# 06_SBCStage_v1.net
KiCad netlist of a schematic drawn in EAGLE
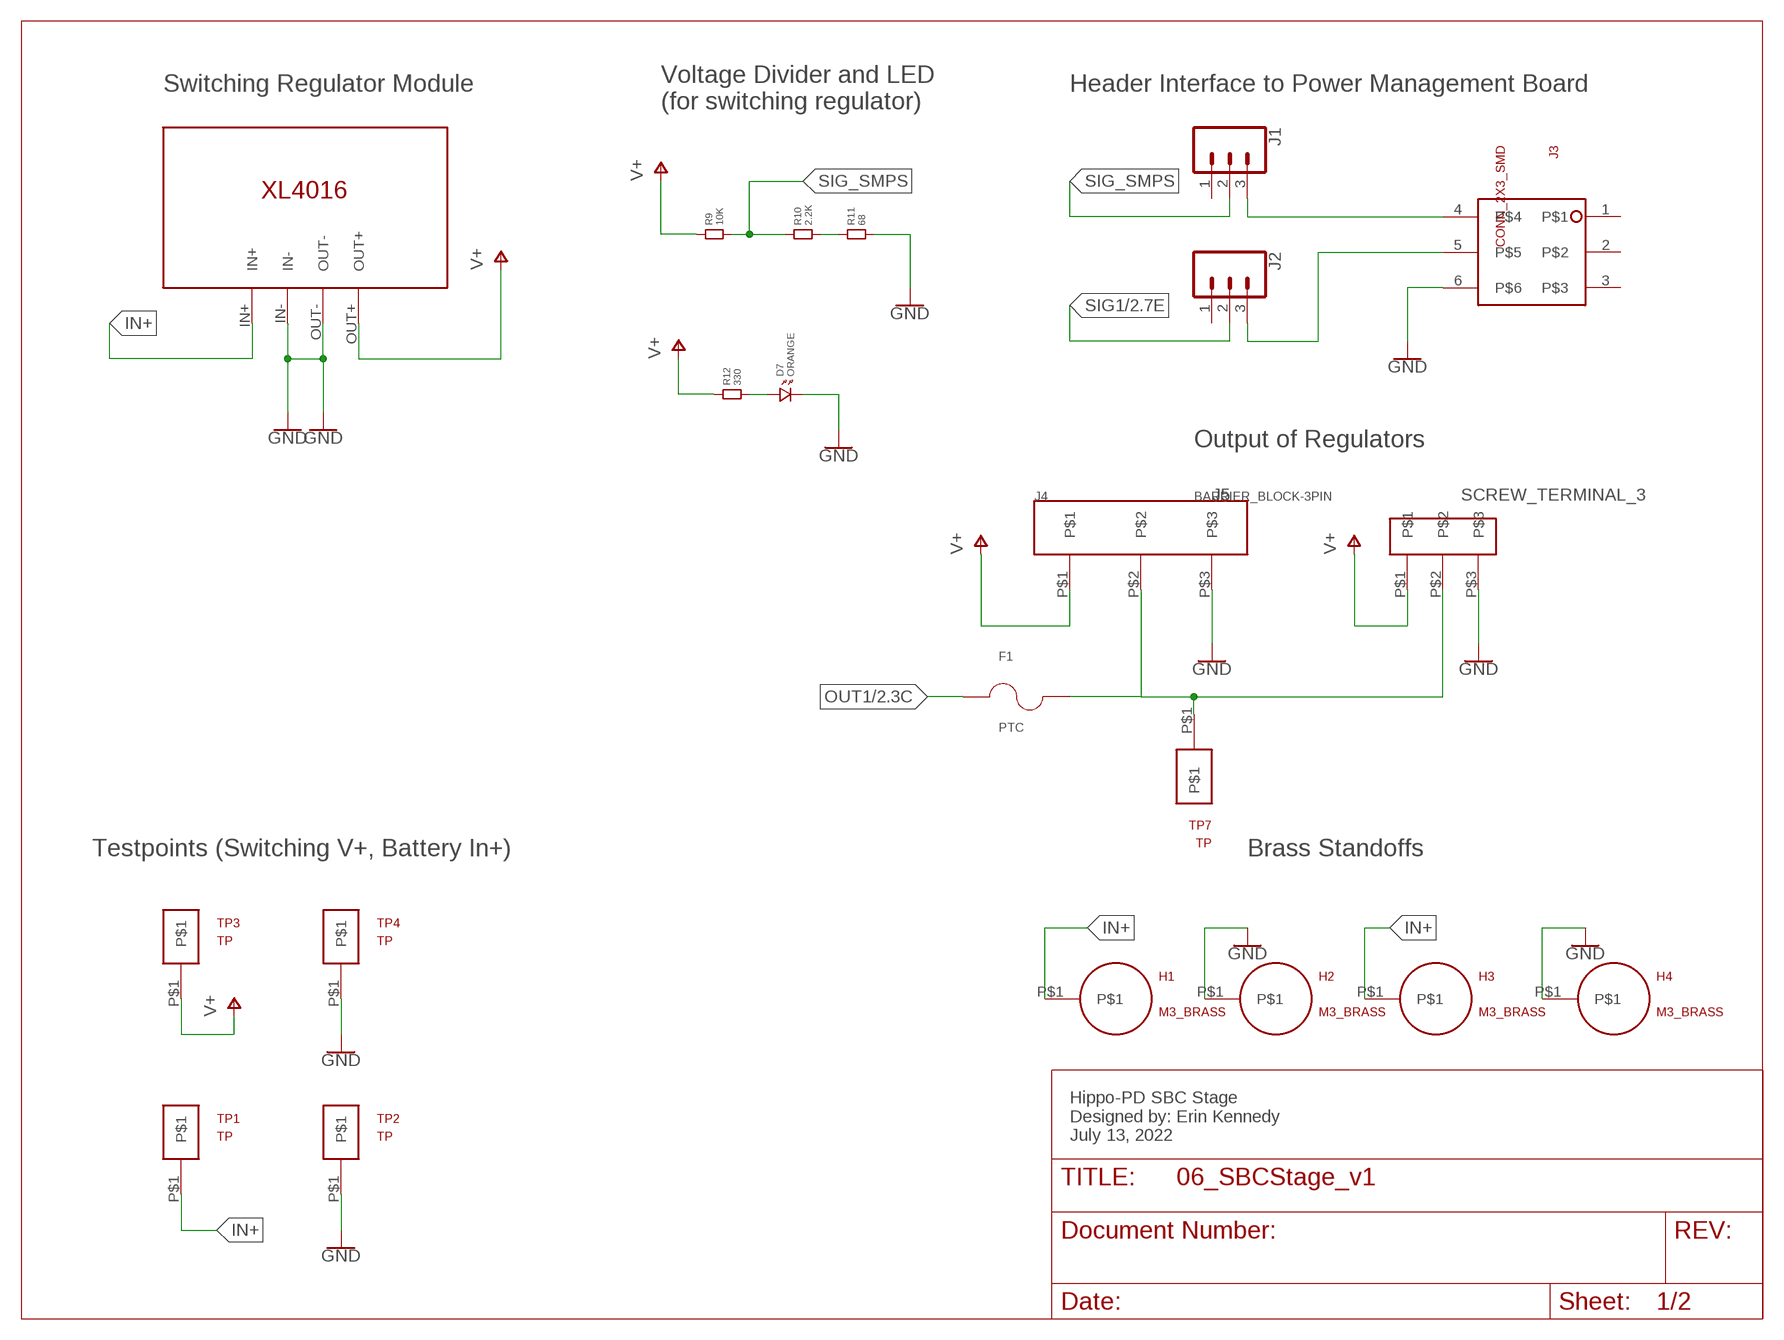
[diagram p0: schematic, sheet 1]
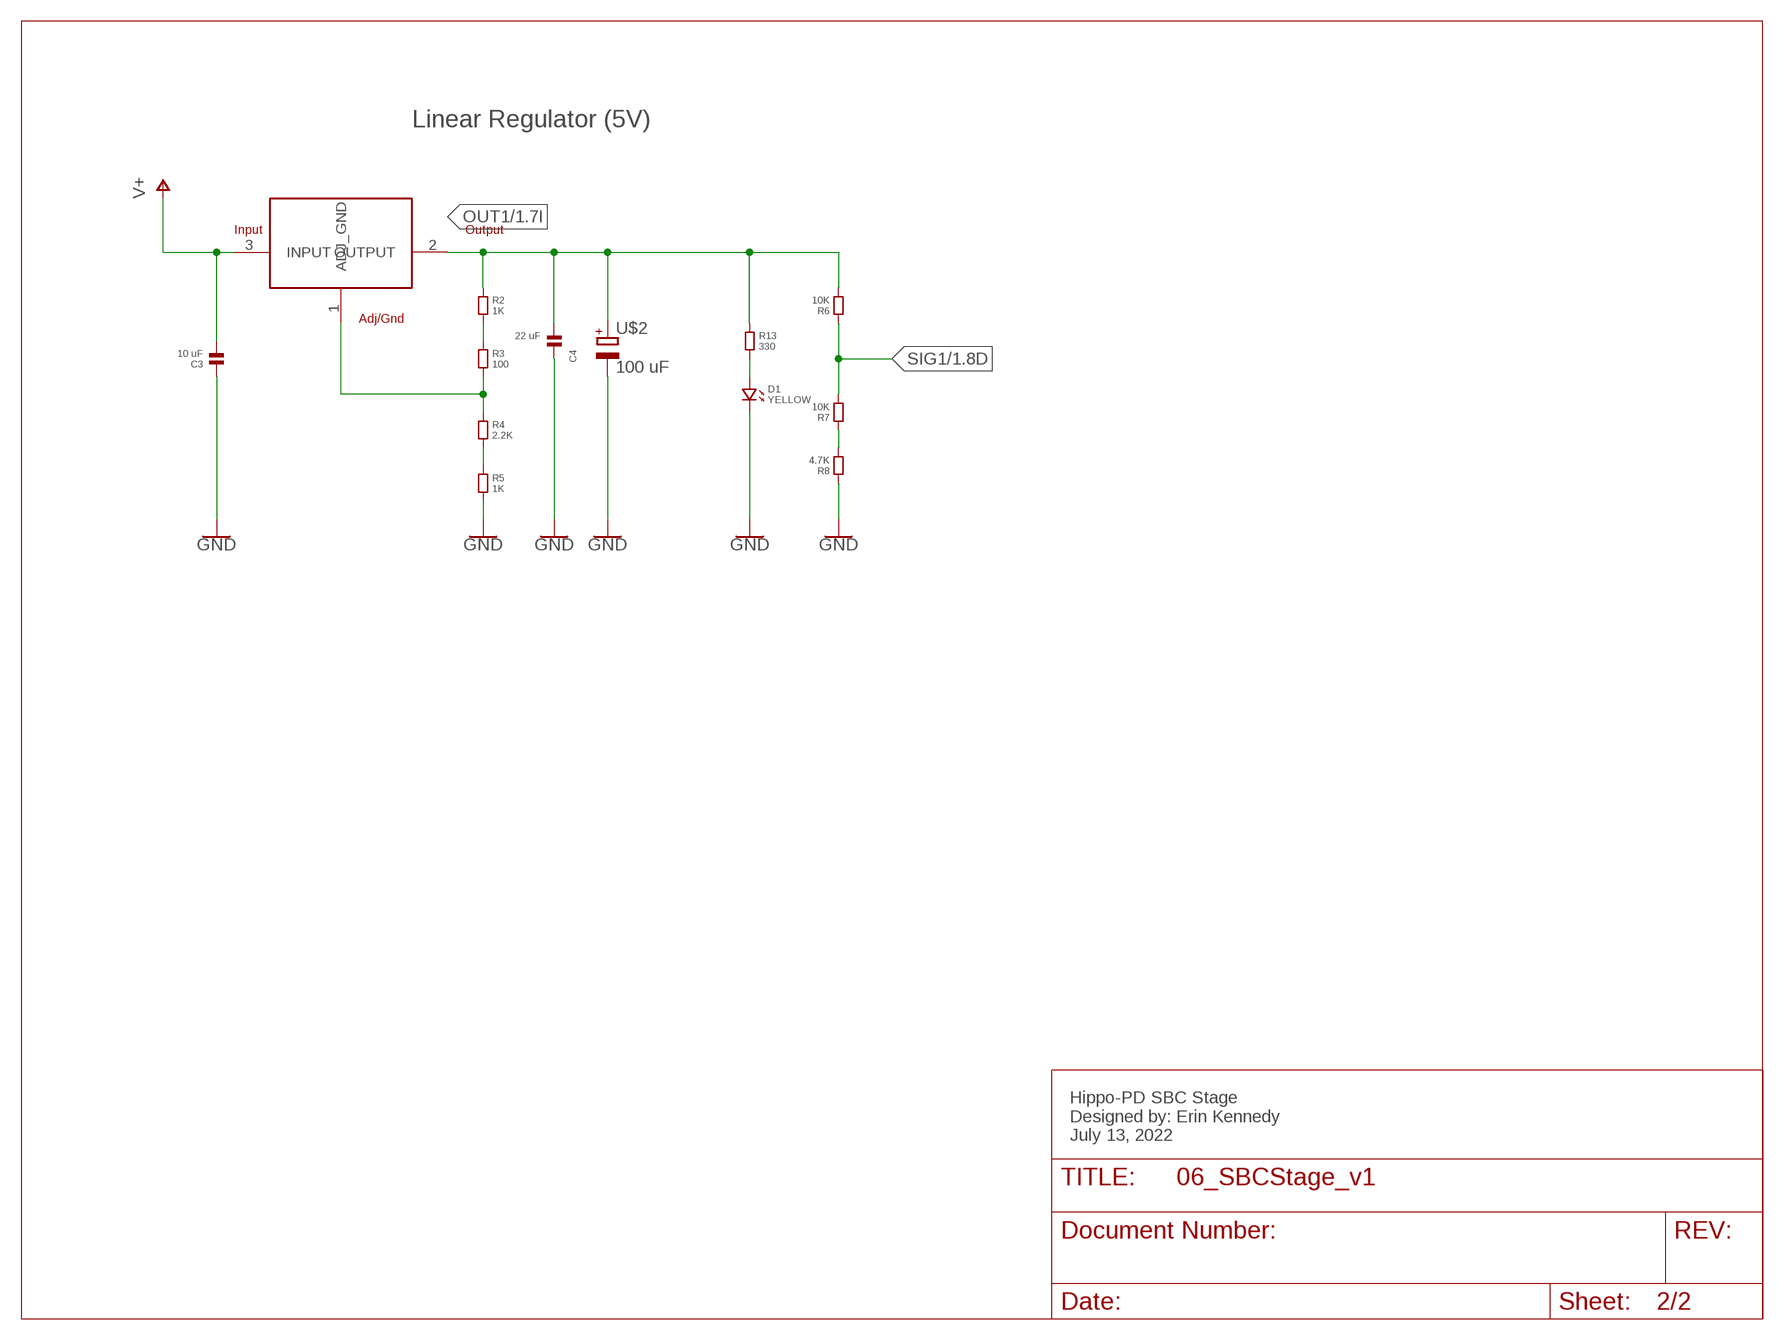
[diagram p1: schematic, sheet 2]

(export (version "E")
  (design (tool "Eeschema 10.0.6"))
  (components
    (comp (ref "D7")
      (value "ORANGE")
      (footprint "eagle-import:1206.LED")
      (libsource (lib "eagle-import") (part "LED.1206"))
    )
    (comp (ref "F1")
      (value "PTC")
      (footprint "eagle-import:PTC")
      (fields (field (name "MF") "Bel Fuse") (field (name "MP") "0ZCF0075AF2C"))
      (libsource (lib "eagle-import") (part "PTC"))
    )
    (comp (ref "H1")
      (value "M3_BRASS")
      (footprint "eagle-import:M3_BRASS")
      (libsource (lib "eagle-import") (part "M3_BRASS"))
    )
    (comp (ref "H2")
      (value "M3_BRASS")
      (footprint "eagle-import:M3_BRASS")
      (libsource (lib "eagle-import") (part "M3_BRASS"))
    )
    (comp (ref "H3")
      (value "M3_BRASS")
      (footprint "eagle-import:M3_BRASS")
      (libsource (lib "eagle-import") (part "M3_BRASS"))
    )
    (comp (ref "H4")
      (value "M3_BRASS")
      (footprint "eagle-import:M3_BRASS")
      (libsource (lib "eagle-import") (part "M3_BRASS"))
    )
    (comp (ref "J1")
      (value "CONN_03")
      (footprint "eagle-import:1X03")
      (libsource (lib "eagle-import") (part "CONN_03"))
    )
    (comp (ref "J2")
      (value "CONN_03")
      (footprint "eagle-import:1X03")
      (libsource (lib "eagle-import") (part "CONN_03"))
    )
    (comp (ref "J3")
      (value "CONN_2X3_SMD")
      (footprint "eagle-import:2X3_SMD_CONNECTOR")
      (libsource (lib "eagle-import") (part "CONN_2X3_SMD"))
    )
    (comp (ref "J4")
      (value "BARRIER_BLOCK-3PIN")
      (footprint "eagle-import:BARRIERBLOCK-3PIN")
      (libsource (lib "eagle-import") (part "BARRIER_BLOCK-3PIN"))
    )
    (comp (ref "J5")
      (value "SCREW_TERMINAL_3")
      (footprint "eagle-import:SCREW_TERM_3")
      (libsource (lib "eagle-import") (part "SCREW_TERMINAL_3"))
    )
    (comp (ref "R9")
      (value "10K")
      (footprint "eagle-import:1206")
      (libsource (lib "eagle-import") (part "RESISTOR.1206"))
    )
    (comp (ref "R10")
      (value "2.2K")
      (footprint "eagle-import:1206")
      (libsource (lib "eagle-import") (part "RESISTOR.1206"))
    )
    (comp (ref "R11")
      (value "68")
      (footprint "eagle-import:1206")
      (libsource (lib "eagle-import") (part "RESISTOR.1206"))
    )
    (comp (ref "R12")
      (value "330")
      (footprint "eagle-import:1206")
      (libsource (lib "eagle-import") (part "RESISTOR.1206"))
    )
    (comp (ref "TP1") (value "TP") (footprint "eagle-import:TP") (libsource (lib "eagle-import") (part "TP")))
    (comp (ref "TP2") (value "TP") (footprint "eagle-import:TP") (libsource (lib "eagle-import") (part "TP")))
    (comp (ref "TP3") (value "TP") (footprint "eagle-import:TP") (libsource (lib "eagle-import") (part "TP")))
    (comp (ref "TP4") (value "TP") (footprint "eagle-import:TP") (libsource (lib "eagle-import") (part "TP")))
    (comp (ref "TP7") (value "TP") (footprint "eagle-import:TP") (libsource (lib "eagle-import") (part "TP")))
    (comp (ref "U1")
      (value "XL4016-DEV")
      (footprint "eagle-import:XL4016-DEV")
      (libsource (lib "eagle-import") (part "XL4016-DEV"))
    )
    (comp (ref "C3")
      (value "10 uF")
      (footprint "eagle-import:1206")
      (libsource (lib "eagle-import") (part "CAPACITOR.1206"))
    )
    (comp (ref "C4")
      (value "22 uF")
      (footprint "eagle-import:1206")
      (libsource (lib "eagle-import") (part "CAPACITOR.1206"))
    )
    (comp (ref "D1")
      (value "YELLOW")
      (footprint "eagle-import:1206.LED")
      (libsource (lib "eagle-import") (part "LED.1206"))
    )
    (comp (ref "R1")
      (value "AZ1084C")
      (footprint "eagle-import:AZ1084C")
      (libsource (lib "eagle-import") (part "AZ1084C"))
    )
    (comp (ref "R2")
      (value "1K")
      (footprint "eagle-import:1206")
      (libsource (lib "eagle-import") (part "RESISTOR.1206"))
    )
    (comp (ref "R3")
      (value "100")
      (footprint "eagle-import:1206")
      (libsource (lib "eagle-import") (part "RESISTOR.1206"))
    )
    (comp (ref "R4")
      (value "2.2K")
      (footprint "eagle-import:1206")
      (libsource (lib "eagle-import") (part "RESISTOR.1206"))
    )
    (comp (ref "R5")
      (value "1K")
      (footprint "eagle-import:1206")
      (libsource (lib "eagle-import") (part "RESISTOR.1206"))
    )
    (comp (ref "R6")
      (value "10K")
      (footprint "eagle-import:1206")
      (libsource (lib "eagle-import") (part "RESISTOR.1206"))
    )
    (comp (ref "R7")
      (value "10K")
      (footprint "eagle-import:1206")
      (libsource (lib "eagle-import") (part "RESISTOR.1206"))
    )
    (comp (ref "R8")
      (value "4.7K")
      (footprint "eagle-import:1206")
      (libsource (lib "eagle-import") (part "RESISTOR.1206"))
    )
    (comp (ref "R13")
      (value "330")
      (footprint "eagle-import:1206")
      (libsource (lib "eagle-import") (part "RESISTOR.1206"))
    )
    (comp (ref "U$2")
      (value "100 uF")
      (footprint "eagle-import:ELECTROLYTIC_CAP")
      (fields (field (name "MF") "Wurth Electronics") (field (name "MP") "865080545012"))
      (libsource (lib "eagle-import") (part "ELECTROLYTIC_CAP"))
    )
  )
  (nets
    (net (code "1") (name "GND") (class "Default")
      (node (ref "C3") (pin "1") (pinfunction "1_1") (pintype "bidirectional"))
      (node (ref "C4") (pin "1") (pinfunction "1_1") (pintype "bidirectional"))
      (node (ref "D1") (pin "P$2") (pinfunction "2_P$2") (pintype "bidirectional"))
      (node (ref "D7") (pin "P$2") (pinfunction "2_P$2") (pintype "bidirectional"))
      (node (ref "H2") (pin "P$1") (pinfunction "P$1_P$1") (pintype "bidirectional"))
      (node (ref "H4") (pin "P$1") (pinfunction "P$1_P$1") (pintype "bidirectional"))
      (node (ref "J3") (pin "6") (pinfunction "P$6_6") (pintype "bidirectional"))
      (node (ref "J4") (pin "P$3") (pinfunction "P$3_P$3") (pintype "bidirectional"))
      (node (ref "J5") (pin "P$3") (pinfunction "P$3_P$3") (pintype "bidirectional"))
      (node (ref "R11") (pin "2") (pinfunction "2_2") (pintype "bidirectional"))
      (node (ref "R5") (pin "2") (pinfunction "2_2") (pintype "bidirectional"))
      (node (ref "R8") (pin "1") (pinfunction "1_1") (pintype "bidirectional"))
      (node (ref "TP2") (pin "P$1") (pinfunction "P$1_P$1") (pintype "bidirectional"))
      (node (ref "TP4") (pin "P$1") (pinfunction "P$1_P$1") (pintype "bidirectional"))
      (node (ref "U$2") (pin "-") (pinfunction "-_-") (pintype "passive"))
      (node (ref "U1") (pin "IN-") (pinfunction "IN-_IN-") (pintype "bidirectional"))
      (node (ref "U1") (pin "OUT-") (pinfunction "OUT-_OUT-") (pintype "bidirectional"))
    )
    (net (code "2") (name "IN+") (class "Default")
      (node (ref "H1") (pin "P$1") (pinfunction "P$1_P$1") (pintype "bidirectional"))
      (node (ref "H3") (pin "P$1") (pinfunction "P$1_P$1") (pintype "bidirectional"))
      (node (ref "TP1") (pin "P$1") (pinfunction "P$1_P$1") (pintype "bidirectional"))
      (node (ref "U1") (pin "IN+") (pinfunction "IN+_IN+") (pintype "bidirectional"))
    )
    (net (code "3") (name "Net-(D1-1)") (class "Default")
      (node (ref "D1") (pin "P$1") (pinfunction "1_P$1") (pintype "bidirectional"))
      (node (ref "R13") (pin "2") (pinfunction "2_2") (pintype "bidirectional"))
    )
    (net (code "4") (name "Net-(D7-1)") (class "Default")
      (node (ref "D7") (pin "P$1") (pinfunction "1_P$1") (pintype "bidirectional"))
      (node (ref "R12") (pin "2") (pinfunction "2_2") (pintype "bidirectional"))
    )
    (net (code "5") (name "Net-(F1-Pad2)") (class "Default")
      (node (ref "F1") (pin "2") (pinfunction "2_2") (pintype "passive"))
      (node (ref "J4") (pin "P$2") (pinfunction "P$2_P$2") (pintype "bidirectional"))
      (node (ref "J5") (pin "P$2") (pinfunction "P$2_P$2") (pintype "bidirectional"))
      (node (ref "TP7") (pin "P$1") (pinfunction "P$1_P$1") (pintype "bidirectional"))
    )
    (net (code "6") (name "Net-(J3-P$4)") (class "Default")
      (node (ref "J1") (pin "3") (pinfunction "3_3") (pintype "passive"))
      (node (ref "J3") (pin "4") (pinfunction "P$4_4") (pintype "bidirectional"))
    )
    (net (code "7") (name "Net-(J3-P$5)") (class "Default")
      (node (ref "J2") (pin "3") (pinfunction "3_3") (pintype "passive"))
      (node (ref "J3") (pin "5") (pinfunction "P$5_5") (pintype "bidirectional"))
    )
    (net (code "8") (name "Net-(R1-ADJ_GND)") (class "Default")
      (node (ref "R1") (pin "1") (pinfunction "ADJ_GND_1") (pintype "bidirectional"))
      (node (ref "R3") (pin "2") (pinfunction "2_2") (pintype "bidirectional"))
      (node (ref "R4") (pin "1") (pinfunction "1_1") (pintype "bidirectional"))
    )
    (net (code "9") (name "Net-(R2-Pad2)") (class "Default")
      (node (ref "R2") (pin "2") (pinfunction "2_2") (pintype "bidirectional"))
      (node (ref "R3") (pin "1") (pinfunction "1_1") (pintype "bidirectional"))
    )
    (net (code "10") (name "Net-(R4-Pad2)") (class "Default")
      (node (ref "R4") (pin "2") (pinfunction "2_2") (pintype "bidirectional"))
      (node (ref "R5") (pin "1") (pinfunction "1_1") (pintype "bidirectional"))
    )
    (net (code "11") (name "Net-(R7-Pad1)") (class "Default")
      (node (ref "R7") (pin "1") (pinfunction "1_1") (pintype "bidirectional"))
      (node (ref "R8") (pin "2") (pinfunction "2_2") (pintype "bidirectional"))
    )
    (net (code "12") (name "Net-(R10-Pad2)") (class "Default")
      (node (ref "R10") (pin "2") (pinfunction "2_2") (pintype "bidirectional"))
      (node (ref "R11") (pin "1") (pinfunction "1_1") (pintype "bidirectional"))
    )
    (net (code "13") (name "OUT1") (class "Default")
      (node (ref "C4") (pin "2") (pinfunction "2_2") (pintype "bidirectional"))
      (node (ref "F1") (pin "1") (pinfunction "1_1") (pintype "passive"))
      (node (ref "R1") (pin "2") (pinfunction "OUTPUT_2") (pintype "bidirectional"))
      (node (ref "R13") (pin "1") (pinfunction "1_1") (pintype "bidirectional"))
      (node (ref "R2") (pin "1") (pinfunction "1_1") (pintype "bidirectional"))
      (node (ref "R6") (pin "2") (pinfunction "2_2") (pintype "bidirectional"))
      (node (ref "U$2") (pin "+") (pinfunction "+_+") (pintype "passive"))
    )
    (net (code "14") (name "SIG1") (class "Default")
      (node (ref "J2") (pin "2") (pinfunction "2_2") (pintype "passive"))
      (node (ref "R6") (pin "1") (pinfunction "1_1") (pintype "bidirectional"))
      (node (ref "R7") (pin "2") (pinfunction "2_2") (pintype "bidirectional"))
    )
    (net (code "15") (name "SIG_SMPS") (class "Default")
      (node (ref "J1") (pin "2") (pinfunction "2_2") (pintype "passive"))
      (node (ref "R10") (pin "1") (pinfunction "1_1") (pintype "bidirectional"))
      (node (ref "R9") (pin "2") (pinfunction "2_2") (pintype "bidirectional"))
    )
    (net (code "16") (name "V+") (class "Default")
      (node (ref "C3") (pin "2") (pinfunction "2_2") (pintype "bidirectional"))
      (node (ref "J4") (pin "P$1") (pinfunction "P$1_P$1") (pintype "bidirectional"))
      (node (ref "J5") (pin "P$1") (pinfunction "P$1_P$1") (pintype "bidirectional"))
      (node (ref "R1") (pin "3") (pinfunction "INPUT_3") (pintype "bidirectional"))
      (node (ref "R12") (pin "1") (pinfunction "1_1") (pintype "bidirectional"))
      (node (ref "R9") (pin "1") (pinfunction "1_1") (pintype "bidirectional"))
      (node (ref "TP3") (pin "P$1") (pinfunction "P$1_P$1") (pintype "bidirectional"))
      (node (ref "U1") (pin "OUT+") (pinfunction "OUT+_OUT+") (pintype "bidirectional"))
    )
    (net (code "17") (name "unconnected-(J1-Pad1)") (class "Default")
      (node (ref "J1") (pin "1") (pinfunction "1_1") (pintype "passive"))
    )
    (net (code "18") (name "unconnected-(J2-Pad1)") (class "Default")
      (node (ref "J2") (pin "1") (pinfunction "1_1") (pintype "passive"))
    )
    (net (code "19") (name "unconnected-(J3-P$1-Pad1)") (class "Default")
      (node (ref "J3") (pin "1") (pinfunction "P$1_1") (pintype "bidirectional"))
    )
    (net (code "20") (name "unconnected-(J3-P$2-Pad2)") (class "Default")
      (node (ref "J3") (pin "2") (pinfunction "P$2_2") (pintype "bidirectional"))
    )
    (net (code "21") (name "unconnected-(J3-P$3-Pad3)") (class "Default")
      (node (ref "J3") (pin "3") (pinfunction "P$3_3") (pintype "bidirectional"))
    )
  )
)
